# GS001.net
KiCad netlist of a schematic drawn in EAGLE
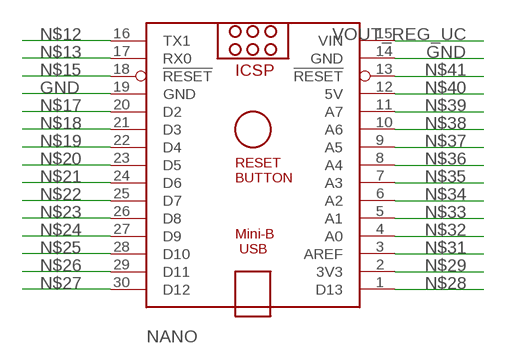
[diagram p0: schematic, sheet 1, part 1 of 2]
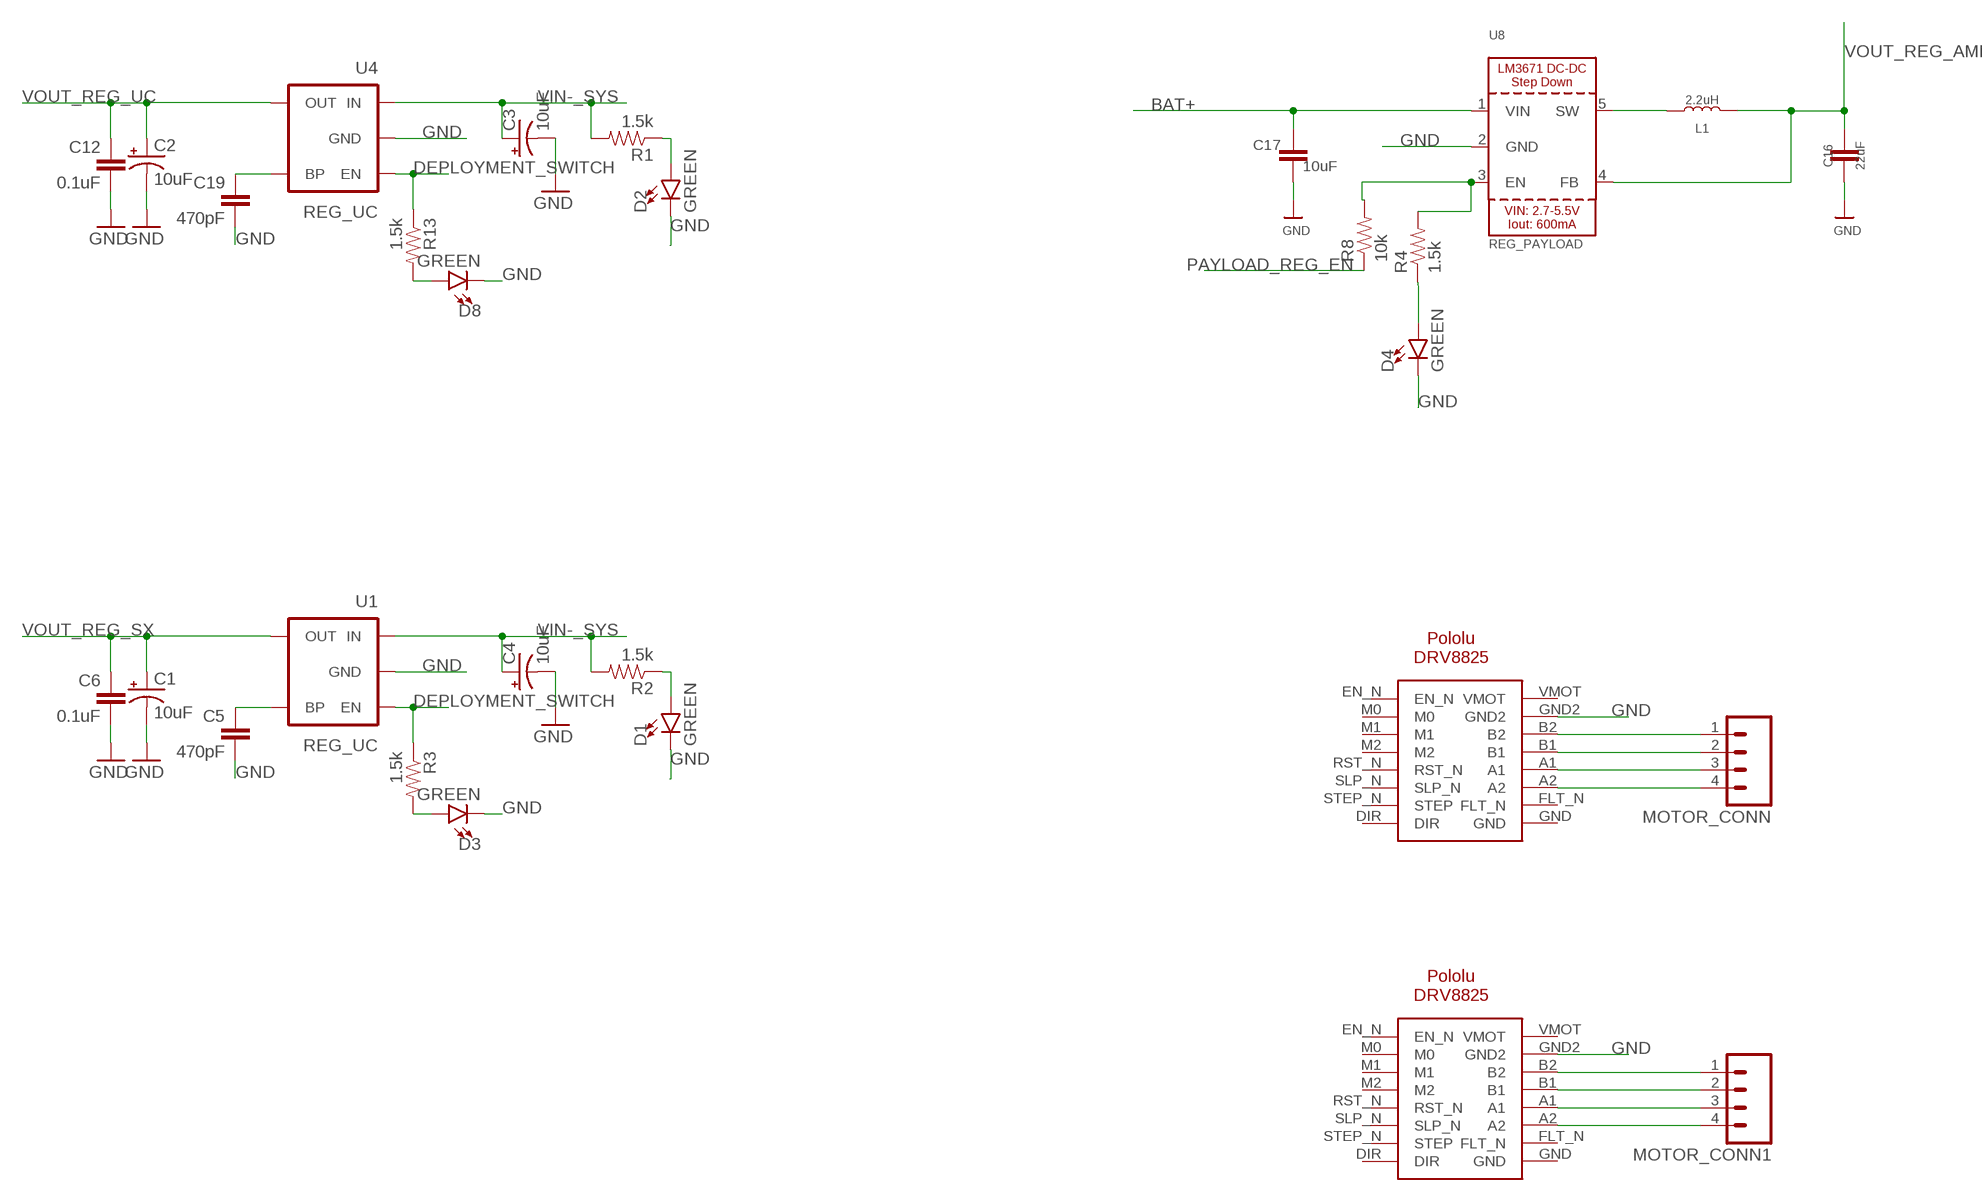
[diagram p1: schematic, sheet 1, part 2 of 2]

(export (version "E")
  (design (tool "Eeschema 10.0.6"))
  (components
    (comp (ref "C1")
      (value "10uF")
      (footprint "eagle-import:0603-POLAR")
      (libsource (lib "eagle-import") (part "10UF-POLAR-0603-6.3V-20%(TANT)"))
    )
    (comp (ref "C2")
      (value "10uF")
      (footprint "eagle-import:0603-POLAR")
      (libsource (lib "eagle-import") (part "10UF-POLAR-0603-6.3V-20%(TANT)"))
    )
    (comp (ref "C3")
      (value "10uF")
      (footprint "eagle-import:0603-POLAR")
      (libsource (lib "eagle-import") (part "10UF-POLAR-0603-6.3V-20%(TANT)"))
    )
    (comp (ref "C4")
      (value "10uF")
      (footprint "eagle-import:0603-POLAR")
      (libsource (lib "eagle-import") (part "10UF-POLAR-0603-6.3V-20%(TANT)"))
    )
    (comp (ref "C5")
      (value "470pF")
      (footprint "eagle-import:0603-CAP")
      (libsource (lib "eagle-import") (part "CAP0603-CAP"))
    )
    (comp (ref "C6")
      (value "0.1uF")
      (footprint "eagle-import:0603-CAP")
      (libsource (lib "eagle-import") (part "CAP0603-CAP"))
    )
    (comp (ref "C12")
      (value "0.1uF")
      (footprint "eagle-import:0603-CAP")
      (libsource (lib "eagle-import") (part "CAP0603-CAP"))
    )
    (comp (ref "C16")
      (value "22uF")
      (footprint "eagle-import:0603")
      (libsource (lib "eagle-import") (part "10UF-0603-6.3V-20%"))
    )
    (comp (ref "C17")
      (value "10uF")
      (footprint "eagle-import:0603")
      (libsource (lib "eagle-import") (part "10UF-0603-6.3V-20%"))
    )
    (comp (ref "C19")
      (value "470pF")
      (footprint "eagle-import:0603-CAP")
      (libsource (lib "eagle-import") (part "CAP0603-CAP"))
    )
    (comp (ref "D1")
      (value "GREEN")
      (footprint "eagle-import:LED-0603")
      (libsource (lib "eagle-import") (part "LED-GREEN0603"))
    )
    (comp (ref "D2")
      (value "GREEN")
      (footprint "eagle-import:LED-0603")
      (libsource (lib "eagle-import") (part "LED-GREEN0603"))
    )
    (comp (ref "D3")
      (value "GREEN")
      (footprint "eagle-import:LED-0603")
      (libsource (lib "eagle-import") (part "LED-GREEN0603"))
    )
    (comp (ref "D4")
      (value "GREEN")
      (footprint "eagle-import:LED-0603")
      (libsource (lib "eagle-import") (part "LED-GREEN0603"))
    )
    (comp (ref "D8")
      (value "GREEN")
      (footprint "eagle-import:LED-0603")
      (libsource (lib "eagle-import") (part "LED-GREEN0603"))
    )
    (comp (ref "L1")
      (value "2.2uH")
      (footprint "eagle-import:0603")
      (libsource (lib "eagle-import") (part "INDUCTOR-0603-33NH"))
    )
    (comp (ref "MOTOR_CONN")
      (value "M04")
      (footprint "eagle-import:04P")
      (libsource (lib "eagle-import") (part "M04"))
    )
    (comp (ref "MOTOR_CONN1")
      (value "M04")
      (footprint "eagle-import:04P")
      (libsource (lib "eagle-import") (part "M04"))
    )
    (comp (ref "NANO")
      (value "ARDUINO_NANO")
      (footprint "eagle-import:ARDUINO_NANO")
      (libsource (lib "eagle-import") (part "ARDUINO_NANO"))
    )
    (comp (ref "R1")
      (value "1.5k")
      (footprint "eagle-import:0603-RES")
      (libsource (lib "eagle-import") (part "RESISTOR0603-RES"))
    )
    (comp (ref "R2")
      (value "1.5k")
      (footprint "eagle-import:0603-RES")
      (libsource (lib "eagle-import") (part "RESISTOR0603-RES"))
    )
    (comp (ref "R3")
      (value "1.5k")
      (footprint "eagle-import:0603-RES")
      (libsource (lib "eagle-import") (part "RESISTOR0603-RES"))
    )
    (comp (ref "R4")
      (value "1.5k")
      (footprint "eagle-import:0603-RES")
      (libsource (lib "eagle-import") (part "RESISTOR0603-RES"))
    )
    (comp (ref "R8")
      (value "10k")
      (footprint "eagle-import:0402-RES")
      (libsource (lib "eagle-import") (part "RESISTOR0402-RES"))
    )
    (comp (ref "R13")
      (value "1.5k")
      (footprint "eagle-import:0603-RES")
      (libsource (lib "eagle-import") (part "RESISTOR0603-RES"))
    )
    (comp (ref "U$1")
      (value "POLOLU-DRV8825")
      (footprint "eagle-import:POLOLU-DRV8825")
      (libsource (lib "eagle-import") (part "POLOLU-DRV8825"))
    )
    (comp (ref "U$4")
      (value "POLOLU-DRV8825")
      (footprint "eagle-import:POLOLU-DRV8825")
      (libsource (lib "eagle-import") (part "POLOLU-DRV8825"))
    )
    (comp (ref "U1")
      (value "REG_UC")
      (footprint "eagle-import:SOT23-5")
      (libsource (lib "eagle-import") (part "V_REG_LDOSMD"))
    )
    (comp (ref "U4")
      (value "REG_UC")
      (footprint "eagle-import:SOT23-5")
      (libsource (lib "eagle-import") (part "V_REG_LDOSMD"))
    )
    (comp (ref "U8")
      (value "REG_PAYLOAD")
      (footprint "eagle-import:SOT23-5")
      (libsource (lib "eagle-import") (part "VREG_LM3671"))
    )
  )
  (nets
    (net (code "1") (name "/BAT+") (class "Default")
      (node (ref "C17") (pin "1") (pinfunction "1_1") (pintype "passive"))
      (node (ref "U8") (pin "1") (pinfunction "VIN_1") (pintype "power_in"))
    )
    (net (code "2") (name "/DEPLOYMENT_SWITCH") (class "Default")
      (node (ref "R13") (pin "1") (pinfunction "1_1") (pintype "passive"))
      (node (ref "R3") (pin "1") (pinfunction "1_1") (pintype "passive"))
      (node (ref "U1") (pin "3") (pinfunction "EN_3") (pintype "input"))
      (node (ref "U4") (pin "3") (pinfunction "EN_3") (pintype "input"))
    )
    (net (code "3") (name "/N$12") (class "Default")
      (node (ref "NANO") (pin "16") (pinfunction "TX1_16") (pintype "bidirectional"))
    )
    (net (code "4") (name "/N$13") (class "Default")
      (node (ref "NANO") (pin "17") (pinfunction "RX0_17") (pintype "bidirectional"))
    )
    (net (code "5") (name "/N$15") (class "Default")
      (node (ref "NANO") (pin "18") (pinfunction "~{RESET}_18") (pintype "input"))
    )
    (net (code "6") (name "/N$17") (class "Default")
      (node (ref "NANO") (pin "20") (pinfunction "D2_20") (pintype "bidirectional"))
    )
    (net (code "7") (name "/N$18") (class "Default")
      (node (ref "NANO") (pin "21") (pinfunction "D3_21") (pintype "bidirectional"))
    )
    (net (code "8") (name "/N$19") (class "Default")
      (node (ref "NANO") (pin "22") (pinfunction "D4_22") (pintype "bidirectional"))
    )
    (net (code "9") (name "/N$20") (class "Default")
      (node (ref "NANO") (pin "23") (pinfunction "D5_23") (pintype "bidirectional"))
    )
    (net (code "10") (name "/N$21") (class "Default")
      (node (ref "NANO") (pin "24") (pinfunction "D6_24") (pintype "bidirectional"))
    )
    (net (code "11") (name "/N$22") (class "Default")
      (node (ref "NANO") (pin "25") (pinfunction "D7_25") (pintype "bidirectional"))
    )
    (net (code "12") (name "/N$23") (class "Default")
      (node (ref "NANO") (pin "26") (pinfunction "D8_26") (pintype "bidirectional"))
    )
    (net (code "13") (name "/N$24") (class "Default")
      (node (ref "NANO") (pin "27") (pinfunction "D9_27") (pintype "bidirectional"))
    )
    (net (code "14") (name "/N$25") (class "Default")
      (node (ref "NANO") (pin "28") (pinfunction "D10_28") (pintype "bidirectional"))
    )
    (net (code "15") (name "/N$26") (class "Default")
      (node (ref "NANO") (pin "29") (pinfunction "D11_29") (pintype "bidirectional"))
    )
    (net (code "16") (name "/N$27") (class "Default")
      (node (ref "NANO") (pin "30") (pinfunction "D12_30") (pintype "bidirectional"))
    )
    (net (code "17") (name "/N$28") (class "Default")
      (node (ref "NANO") (pin "1") (pinfunction "D13_1") (pintype "bidirectional"))
    )
    (net (code "18") (name "/N$29") (class "Default")
      (node (ref "NANO") (pin "2") (pinfunction "3V3_2") (pintype "output"))
    )
    (net (code "19") (name "/N$31") (class "Default")
      (node (ref "NANO") (pin "3") (pinfunction "AREF_3") (pintype "input"))
    )
    (net (code "20") (name "/N$32") (class "Default")
      (node (ref "NANO") (pin "4") (pinfunction "A0_4") (pintype "bidirectional"))
    )
    (net (code "21") (name "/N$33") (class "Default")
      (node (ref "NANO") (pin "5") (pinfunction "A1_5") (pintype "bidirectional"))
    )
    (net (code "22") (name "/N$34") (class "Default")
      (node (ref "NANO") (pin "6") (pinfunction "A2_6") (pintype "bidirectional"))
    )
    (net (code "23") (name "/N$35") (class "Default")
      (node (ref "NANO") (pin "7") (pinfunction "A3_7") (pintype "bidirectional"))
    )
    (net (code "24") (name "/N$36") (class "Default")
      (node (ref "NANO") (pin "8") (pinfunction "A4_8") (pintype "bidirectional"))
    )
    (net (code "25") (name "/N$37") (class "Default")
      (node (ref "NANO") (pin "9") (pinfunction "A5_9") (pintype "bidirectional"))
    )
    (net (code "26") (name "/N$38") (class "Default")
      (node (ref "NANO") (pin "10") (pinfunction "A6_10") (pintype "bidirectional"))
    )
    (net (code "27") (name "/N$39") (class "Default")
      (node (ref "NANO") (pin "11") (pinfunction "A7_11") (pintype "bidirectional"))
    )
    (net (code "28") (name "/N$40") (class "Default")
      (node (ref "NANO") (pin "12") (pinfunction "5V_12") (pintype "power_in"))
    )
    (net (code "29") (name "/N$41") (class "Default")
      (node (ref "NANO") (pin "13") (pinfunction "~{RESET}_13") (pintype "input"))
    )
    (net (code "30") (name "/PAYLOAD_REG_EN") (class "Default")
      (node (ref "R8") (pin "1") (pinfunction "1_1") (pintype "passive"))
    )
    (net (code "31") (name "/VIN-_SYS") (class "Default")
      (node (ref "C3") (pin "+") (pinfunction "+_+") (pintype "passive"))
      (node (ref "C4") (pin "+") (pinfunction "+_+") (pintype "passive"))
      (node (ref "R1") (pin "2") (pinfunction "2_2") (pintype "passive"))
      (node (ref "R2") (pin "2") (pinfunction "2_2") (pintype "passive"))
      (node (ref "U1") (pin "1") (pinfunction "IN_1") (pintype "input"))
      (node (ref "U4") (pin "1") (pinfunction "IN_1") (pintype "input"))
    )
    (net (code "32") (name "/VOUT_REG_AMP") (class "Default")
      (node (ref "C16") (pin "1") (pinfunction "1_1") (pintype "passive"))
      (node (ref "L1") (pin "2") (pinfunction "2_2") (pintype "passive"))
      (node (ref "U8") (pin "4") (pinfunction "FB_4") (pintype "power_in"))
    )
    (net (code "33") (name "/VOUT_REG_SX") (class "Default")
      (node (ref "C1") (pin "+") (pinfunction "+_+") (pintype "passive"))
      (node (ref "C6") (pin "1") (pinfunction "1_1") (pintype "passive"))
      (node (ref "U1") (pin "5") (pinfunction "OUT_5") (pintype "passive"))
    )
    (net (code "34") (name "/VOUT_REG_UC") (class "Default")
      (node (ref "C12") (pin "1") (pinfunction "1_1") (pintype "passive"))
      (node (ref "C2") (pin "+") (pinfunction "+_+") (pintype "passive"))
      (node (ref "NANO") (pin "15") (pinfunction "VIN_15") (pintype "power_in"))
      (node (ref "U4") (pin "5") (pinfunction "OUT_5") (pintype "passive"))
    )
    (net (code "35") (name "GND") (class "Default")
      (node (ref "C1") (pin "-") (pinfunction "-_-") (pintype "passive"))
      (node (ref "C12") (pin "2") (pinfunction "2_2") (pintype "passive"))
      (node (ref "C16") (pin "2") (pinfunction "2_2") (pintype "passive"))
      (node (ref "C17") (pin "2") (pinfunction "2_2") (pintype "passive"))
      (node (ref "C19") (pin "2") (pinfunction "2_2") (pintype "passive"))
      (node (ref "C2") (pin "-") (pinfunction "-_-") (pintype "passive"))
      (node (ref "C3") (pin "-") (pinfunction "-_-") (pintype "passive"))
      (node (ref "C4") (pin "-") (pinfunction "-_-") (pintype "passive"))
      (node (ref "C5") (pin "2") (pinfunction "2_2") (pintype "passive"))
      (node (ref "C6") (pin "2") (pinfunction "2_2") (pintype "passive"))
      (node (ref "D1") (pin "C") (pinfunction "C_C") (pintype "passive"))
      (node (ref "D2") (pin "C") (pinfunction "C_C") (pintype "passive"))
      (node (ref "D3") (pin "C") (pinfunction "C_C") (pintype "passive"))
      (node (ref "D4") (pin "C") (pinfunction "C_C") (pintype "passive"))
      (node (ref "D8") (pin "C") (pinfunction "C_C") (pintype "passive"))
      (node (ref "NANO") (pin "14") (pinfunction "GND_14") (pintype "power_in"))
      (node (ref "NANO") (pin "19") (pinfunction "GND_19") (pintype "power_in"))
      (node (ref "U$1") (pin "GND2") (pinfunction "GND2_GND2") (pintype "bidirectional"))
      (node (ref "U$4") (pin "GND2") (pinfunction "GND2_GND2") (pintype "bidirectional"))
      (node (ref "U1") (pin "2") (pinfunction "GND_2") (pintype "input"))
      (node (ref "U4") (pin "2") (pinfunction "GND_2") (pintype "input"))
      (node (ref "U8") (pin "2") (pinfunction "GND_2") (pintype "power_in"))
    )
    (net (code "36") (name "Net-(D1-PadA)") (class "Default")
      (node (ref "D1") (pin "A") (pinfunction "A_A") (pintype "passive"))
      (node (ref "R2") (pin "1") (pinfunction "1_1") (pintype "passive"))
    )
    (net (code "37") (name "Net-(D2-PadA)") (class "Default")
      (node (ref "D2") (pin "A") (pinfunction "A_A") (pintype "passive"))
      (node (ref "R1") (pin "1") (pinfunction "1_1") (pintype "passive"))
    )
    (net (code "38") (name "Net-(D3-PadA)") (class "Default")
      (node (ref "D3") (pin "A") (pinfunction "A_A") (pintype "passive"))
      (node (ref "R3") (pin "2") (pinfunction "2_2") (pintype "passive"))
    )
    (net (code "39") (name "Net-(D4-PadA)") (class "Default")
      (node (ref "D4") (pin "A") (pinfunction "A_A") (pintype "passive"))
      (node (ref "R4") (pin "1") (pinfunction "1_1") (pintype "passive"))
    )
    (net (code "40") (name "Net-(D8-PadA)") (class "Default")
      (node (ref "D8") (pin "A") (pinfunction "A_A") (pintype "passive"))
      (node (ref "R13") (pin "2") (pinfunction "2_2") (pintype "passive"))
    )
    (net (code "41") (name "Net-(MOTOR_CONN-Pad1)") (class "Default")
      (node (ref "MOTOR_CONN") (pin "1") (pinfunction "1_1") (pintype "passive"))
      (node (ref "U$1") (pin "B2") (pinfunction "B2_B2") (pintype "bidirectional"))
    )
    (net (code "42") (name "Net-(MOTOR_CONN-Pad2)") (class "Default")
      (node (ref "MOTOR_CONN") (pin "2") (pinfunction "2_2") (pintype "passive"))
      (node (ref "U$1") (pin "B1") (pinfunction "B1_B1") (pintype "bidirectional"))
    )
    (net (code "43") (name "Net-(MOTOR_CONN-Pad3)") (class "Default")
      (node (ref "MOTOR_CONN") (pin "3") (pinfunction "3_3") (pintype "passive"))
      (node (ref "U$1") (pin "A1") (pinfunction "A1_A1") (pintype "bidirectional"))
    )
    (net (code "44") (name "Net-(MOTOR_CONN-Pad4)") (class "Default")
      (node (ref "MOTOR_CONN") (pin "4") (pinfunction "4_4") (pintype "passive"))
      (node (ref "U$1") (pin "A2") (pinfunction "A2_A2") (pintype "bidirectional"))
    )
    (net (code "45") (name "Net-(MOTOR_CONN1-Pad1)") (class "Default")
      (node (ref "MOTOR_CONN1") (pin "1") (pinfunction "1_1") (pintype "passive"))
      (node (ref "U$4") (pin "B2") (pinfunction "B2_B2") (pintype "bidirectional"))
    )
    (net (code "46") (name "Net-(MOTOR_CONN1-Pad2)") (class "Default")
      (node (ref "MOTOR_CONN1") (pin "2") (pinfunction "2_2") (pintype "passive"))
      (node (ref "U$4") (pin "B1") (pinfunction "B1_B1") (pintype "bidirectional"))
    )
    (net (code "47") (name "Net-(MOTOR_CONN1-Pad3)") (class "Default")
      (node (ref "MOTOR_CONN1") (pin "3") (pinfunction "3_3") (pintype "passive"))
      (node (ref "U$4") (pin "A1") (pinfunction "A1_A1") (pintype "bidirectional"))
    )
    (net (code "48") (name "Net-(MOTOR_CONN1-Pad4)") (class "Default")
      (node (ref "MOTOR_CONN1") (pin "4") (pinfunction "4_4") (pintype "passive"))
      (node (ref "U$4") (pin "A2") (pinfunction "A2_A2") (pintype "bidirectional"))
    )
    (net (code "49") (name "Net-(U1-BP)") (class "Default")
      (node (ref "C5") (pin "1") (pinfunction "1_1") (pintype "passive"))
      (node (ref "U1") (pin "4") (pinfunction "BP_4") (pintype "input"))
    )
    (net (code "50") (name "Net-(U4-BP)") (class "Default")
      (node (ref "C19") (pin "1") (pinfunction "1_1") (pintype "passive"))
      (node (ref "U4") (pin "4") (pinfunction "BP_4") (pintype "input"))
    )
    (net (code "51") (name "Net-(U8-EN)") (class "Default")
      (node (ref "R4") (pin "2") (pinfunction "2_2") (pintype "passive"))
      (node (ref "R8") (pin "2") (pinfunction "2_2") (pintype "passive"))
      (node (ref "U8") (pin "3") (pinfunction "EN_3") (pintype "input"))
    )
    (net (code "52") (name "Net-(U8-SW)") (class "Default")
      (node (ref "L1") (pin "1") (pinfunction "1_1") (pintype "passive"))
      (node (ref "U8") (pin "5") (pinfunction "SW_5") (pintype "output"))
    )
    (net (code "53") (name "unconnected-(U$1-PadDIR)") (class "Default")
      (node (ref "U$1") (pin "DIR") (pinfunction "DIR_DIR") (pintype "bidirectional"))
    )
    (net (code "54") (name "unconnected-(U$1-PadEN_N)") (class "Default")
      (node (ref "U$1") (pin "EN_N") (pinfunction "EN_N_EN_N") (pintype "bidirectional"))
    )
    (net (code "55") (name "unconnected-(U$1-PadFLT_N)") (class "Default")
      (node (ref "U$1") (pin "FLT_N") (pinfunction "FLT_N_FLT_N") (pintype "bidirectional"))
    )
    (net (code "56") (name "unconnected-(U$1-PadGND)") (class "Default")
      (node (ref "U$1") (pin "GND") (pinfunction "GND_GND") (pintype "bidirectional"))
    )
    (net (code "57") (name "unconnected-(U$1-PadM0)") (class "Default")
      (node (ref "U$1") (pin "M0") (pinfunction "M0_M0") (pintype "bidirectional"))
    )
    (net (code "58") (name "unconnected-(U$1-PadM1)") (class "Default")
      (node (ref "U$1") (pin "M1") (pinfunction "M1_M1") (pintype "bidirectional"))
    )
    (net (code "59") (name "unconnected-(U$1-PadM2)") (class "Default")
      (node (ref "U$1") (pin "M2") (pinfunction "M2_M2") (pintype "bidirectional"))
    )
    (net (code "60") (name "unconnected-(U$1-PadRST_N)") (class "Default")
      (node (ref "U$1") (pin "RST_N") (pinfunction "RST_N_RST_N") (pintype "bidirectional"))
    )
    (net (code "61") (name "unconnected-(U$1-PadSLP_N)") (class "Default")
      (node (ref "U$1") (pin "SLP_N") (pinfunction "SLP_N_SLP_N") (pintype "bidirectional"))
    )
    (net (code "62") (name "unconnected-(U$1-PadVMOT)") (class "Default")
      (node (ref "U$1") (pin "VMOT") (pinfunction "VMOT_VMOT") (pintype "bidirectional"))
    )
    (net (code "63") (name "unconnected-(U$1-STEP-PadSTEP_N)") (class "Default")
      (node (ref "U$1") (pin "STEP_N") (pinfunction "STEP_STEP_N") (pintype "bidirectional"))
    )
    (net (code "64") (name "unconnected-(U$4-PadDIR)") (class "Default")
      (node (ref "U$4") (pin "DIR") (pinfunction "DIR_DIR") (pintype "bidirectional"))
    )
    (net (code "65") (name "unconnected-(U$4-PadEN_N)") (class "Default")
      (node (ref "U$4") (pin "EN_N") (pinfunction "EN_N_EN_N") (pintype "bidirectional"))
    )
    (net (code "66") (name "unconnected-(U$4-PadFLT_N)") (class "Default")
      (node (ref "U$4") (pin "FLT_N") (pinfunction "FLT_N_FLT_N") (pintype "bidirectional"))
    )
    (net (code "67") (name "unconnected-(U$4-PadGND)") (class "Default")
      (node (ref "U$4") (pin "GND") (pinfunction "GND_GND") (pintype "bidirectional"))
    )
    (net (code "68") (name "unconnected-(U$4-PadM0)") (class "Default")
      (node (ref "U$4") (pin "M0") (pinfunction "M0_M0") (pintype "bidirectional"))
    )
    (net (code "69") (name "unconnected-(U$4-PadM1)") (class "Default")
      (node (ref "U$4") (pin "M1") (pinfunction "M1_M1") (pintype "bidirectional"))
    )
    (net (code "70") (name "unconnected-(U$4-PadM2)") (class "Default")
      (node (ref "U$4") (pin "M2") (pinfunction "M2_M2") (pintype "bidirectional"))
    )
    (net (code "71") (name "unconnected-(U$4-PadRST_N)") (class "Default")
      (node (ref "U$4") (pin "RST_N") (pinfunction "RST_N_RST_N") (pintype "bidirectional"))
    )
    (net (code "72") (name "unconnected-(U$4-PadSLP_N)") (class "Default")
      (node (ref "U$4") (pin "SLP_N") (pinfunction "SLP_N_SLP_N") (pintype "bidirectional"))
    )
    (net (code "73") (name "unconnected-(U$4-PadVMOT)") (class "Default")
      (node (ref "U$4") (pin "VMOT") (pinfunction "VMOT_VMOT") (pintype "bidirectional"))
    )
    (net (code "74") (name "unconnected-(U$4-STEP-PadSTEP_N)") (class "Default")
      (node (ref "U$4") (pin "STEP_N") (pinfunction "STEP_STEP_N") (pintype "bidirectional"))
    )
  )
)
